# Ethernet.net
KiCad netlist of a schematic drawn in Altium Designer
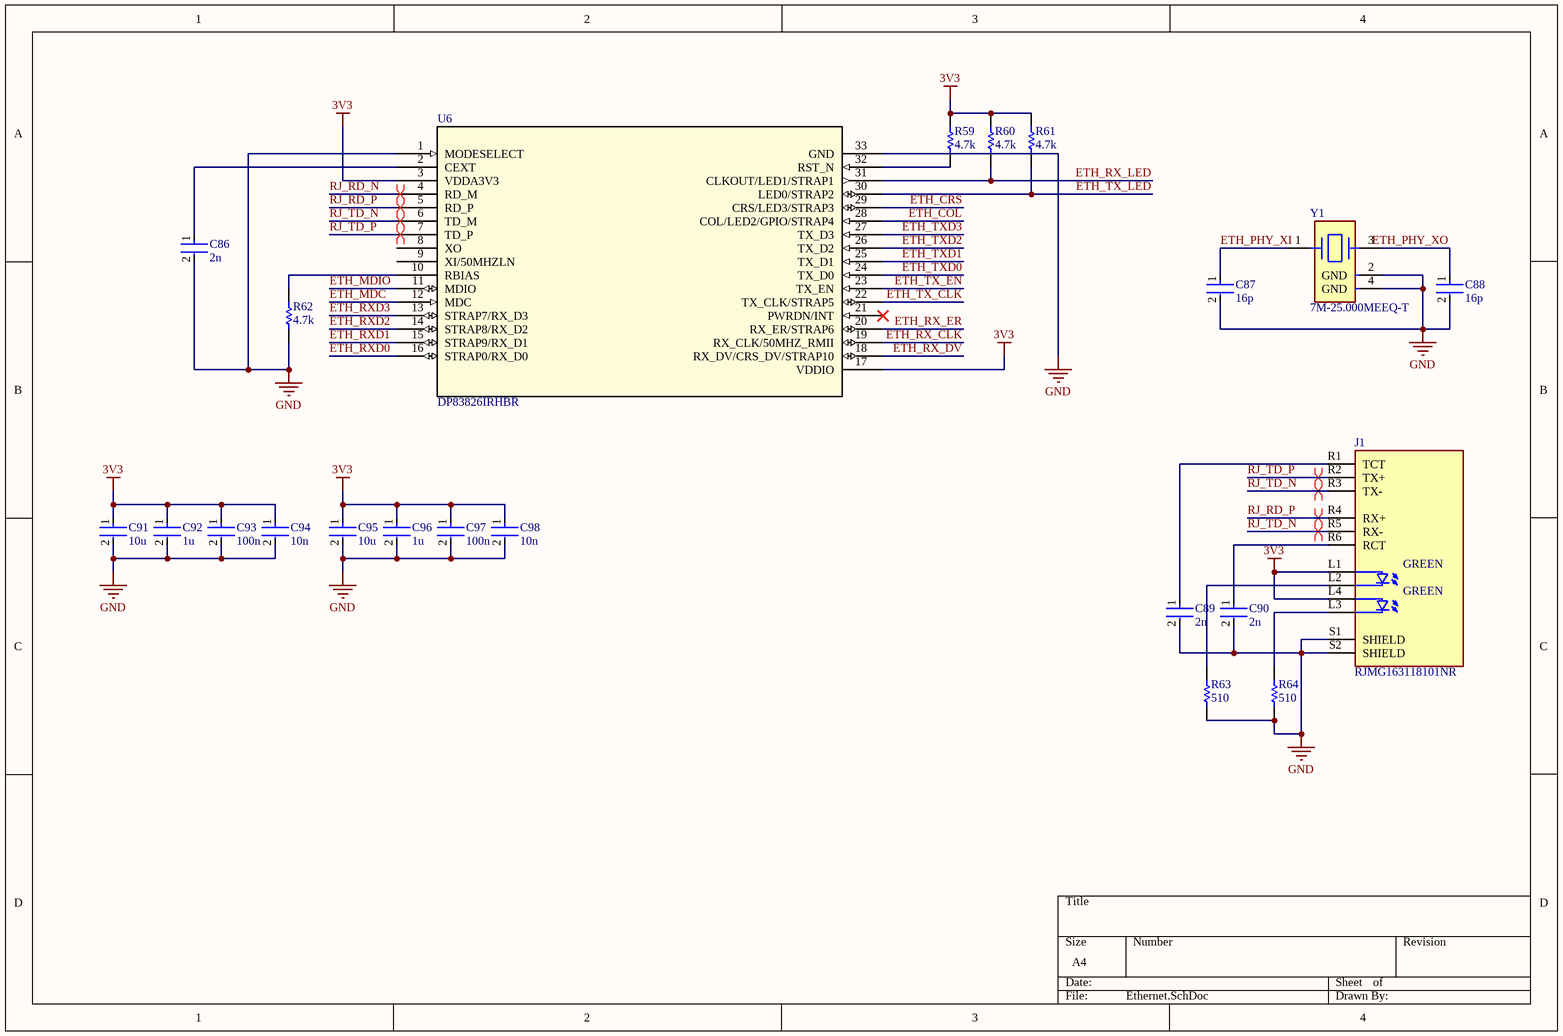
[diagram p0: Ethernet.SchDoc]

(export (version "E")
  (design (tool "Eeschema 10.0.6"))
  (components
    (comp (ref "C86")
      (value "2n")
      (footprint "FP-C0603C-CF-MFG")
      (description "CAP CER 0.1UF 50V X7R 0603")
      (fields (field (name "TOLERANCE") "0.1") (field (name "MANUFACTURER") "KEMET"))
      (libsource (lib "Altium Content Vault") (part "b4654b650e69147ec39a6b967a45e02"))
    )
    (comp (ref "C87")
      (value "16p")
      (footprint "FP-C0603C-CF-MFG")
      (description "CAP CER 0.1UF 50V X7R 0603")
      (fields (field (name "TOLERANCE") "0.1") (field (name "MANUFACTURER") "KEMET"))
      (libsource (lib "Altium Content Vault") (part "b4654b650e69147ec39a6b967a45e02"))
    )
    (comp (ref "C88")
      (value "16p")
      (footprint "FP-C0603C-CF-MFG")
      (description "CAP CER 0.1UF 50V X7R 0603")
      (fields (field (name "TOLERANCE") "0.1") (field (name "MANUFACTURER") "KEMET"))
      (libsource (lib "Altium Content Vault") (part "b4654b650e69147ec39a6b967a45e02"))
    )
    (comp (ref "C89")
      (value "2n")
      (footprint "FP-C0603C-CF-MFG")
      (description "CAP CER 0.1UF 50V X7R 0603")
      (fields (field (name "TOLERANCE") "0.1") (field (name "MANUFACTURER") "KEMET"))
      (libsource (lib "Altium Content Vault") (part "b4654b650e69147ec39a6b967a45e02"))
    )
    (comp (ref "C90")
      (value "2n")
      (footprint "FP-C0603C-CF-MFG")
      (description "CAP CER 0.1UF 50V X7R 0603")
      (fields (field (name "TOLERANCE") "0.1") (field (name "MANUFACTURER") "KEMET"))
      (libsource (lib "Altium Content Vault") (part "b4654b650e69147ec39a6b967a45e02"))
    )
    (comp (ref "C91")
      (value "10u")
      (footprint "FP-CC0805-0_85-MFG")
      (description "CAP CER 0.1UF 50V X7R 0805")
      (fields (field (name "TOLERANCE") "0.1") (field (name "MANUFACTURER PART NUMBER") "CC0805KRX7R9BB104"))
      (libsource (lib "Altium Content Vault") (part "11868f565c42a9108669ba33697ecf6"))
    )
    (comp (ref "C92")
      (value "1u")
      (footprint "FP-CC0805-0_85-MFG")
      (description "CAP CER 0.1UF 50V X7R 0805")
      (fields (field (name "TOLERANCE") "0.1") (field (name "MANUFACTURER PART NUMBER") "CC0805KRX7R9BB104"))
      (libsource (lib "Altium Content Vault") (part "11868f565c42a9108669ba33697ecf6"))
    )
    (comp (ref "C93")
      (value "100n")
      (footprint "FP-C0603C-CF-MFG")
      (description "CAP CER 0.1UF 50V X7R 0603")
      (fields (field (name "TOLERANCE") "0.1") (field (name "MANUFACTURER") "KEMET"))
      (libsource (lib "Altium Content Vault") (part "b4654b650e69147ec39a6b967a45e02"))
    )
    (comp (ref "C94")
      (value "10n")
      (footprint "FP-C0603C-CF-MFG")
      (description "CAP CER 0.1UF 50V X7R 0603")
      (fields (field (name "TOLERANCE") "0.1") (field (name "MANUFACTURER") "KEMET"))
      (libsource (lib "Altium Content Vault") (part "b4654b650e69147ec39a6b967a45e02"))
    )
    (comp (ref "C95")
      (value "10u")
      (footprint "FP-CC0805-0_85-MFG")
      (description "CAP CER 0.1UF 50V X7R 0805")
      (fields (field (name "TOLERANCE") "0.1") (field (name "MANUFACTURER PART NUMBER") "CC0805KRX7R9BB104"))
      (libsource (lib "Altium Content Vault") (part "11868f565c42a9108669ba33697ecf6"))
    )
    (comp (ref "C96")
      (value "1u")
      (footprint "FP-CC0805-0_85-MFG")
      (description "CAP CER 0.1UF 50V X7R 0805")
      (fields (field (name "TOLERANCE") "0.1") (field (name "MANUFACTURER PART NUMBER") "CC0805KRX7R9BB104"))
      (libsource (lib "Altium Content Vault") (part "11868f565c42a9108669ba33697ecf6"))
    )
    (comp (ref "C97")
      (value "100n")
      (footprint "FP-C0603C-CF-MFG")
      (description "CAP CER 0.1UF 50V X7R 0603")
      (fields (field (name "TOLERANCE") "0.1") (field (name "MANUFACTURER") "KEMET"))
      (libsource (lib "Altium Content Vault") (part "b4654b650e69147ec39a6b967a45e02"))
    )
    (comp (ref "C98")
      (value "10n")
      (footprint "FP-C0603C-CF-MFG")
      (description "CAP CER 0.1UF 50V X7R 0603")
      (fields (field (name "TOLERANCE") "0.1") (field (name "MANUFACTURER") "KEMET"))
      (libsource (lib "Altium Content Vault") (part "b4654b650e69147ec39a6b967a45e02"))
    )
    (comp (ref "J1")
      (value "RJMG163118101NR")
      (footprint "AMPHENOL_RJMG163118101NR")
      (libsource (lib "Master") (part "RJMG163118101NR"))
    )
    (comp (ref "R59")
      (value "4.7k")
      (footprint "RESC1609X50X30NL8T20")
      (description "Chip Resistor, 10 KOhm, +/- 1%, 100 mW, -55 to 155 degC, 0603 (1608 Metric), RoHS, Tape and Reel")
      (fields (field (name "MANUFACTURER") "Vishay Semiconductor"))
      (libsource (lib "Altium Content Vault") (part "RES-2"))
    )
    (comp (ref "R60")
      (value "4.7k")
      (footprint "RESC1609X50X30NL8T20")
      (description "Chip Resistor, 10 KOhm, +/- 1%, 100 mW, -55 to 155 degC, 0603 (1608 Metric), RoHS, Tape and Reel")
      (fields (field (name "MANUFACTURER") "Vishay Semiconductor"))
      (libsource (lib "Altium Content Vault") (part "RES-2"))
    )
    (comp (ref "R61")
      (value "4.7k")
      (footprint "RESC1609X50X30NL8T20")
      (description "Chip Resistor, 10 KOhm, +/- 1%, 100 mW, -55 to 155 degC, 0603 (1608 Metric), RoHS, Tape and Reel")
      (fields (field (name "MANUFACTURER") "Vishay Semiconductor"))
      (libsource (lib "Altium Content Vault") (part "RES-2"))
    )
    (comp (ref "R62")
      (value "4.7k")
      (footprint "RESC1609X50X30NL8T20")
      (description "Chip Resistor, 10 KOhm, +/- 1%, 100 mW, -55 to 155 degC, 0603 (1608 Metric), RoHS, Tape and Reel")
      (fields (field (name "MANUFACTURER") "Vishay Semiconductor"))
      (libsource (lib "Altium Content Vault") (part "RES-2"))
    )
    (comp (ref "R63")
      (value "510")
      (footprint "RESC1609X50X30NL8T20")
      (description "Chip Resistor, 10 KOhm, +/- 1%, 100 mW, -55 to 155 degC, 0603 (1608 Metric), RoHS, Tape and Reel")
      (fields (field (name "MANUFACTURER") "Vishay Semiconductor"))
      (libsource (lib "Altium Content Vault") (part "RES-2"))
    )
    (comp (ref "R64")
      (value "510")
      (footprint "RESC1609X50X30NL8T20")
      (description "Chip Resistor, 10 KOhm, +/- 1%, 100 mW, -55 to 155 degC, 0603 (1608 Metric), RoHS, Tape and Reel")
      (fields (field (name "MANUFACTURER") "Vishay Semiconductor"))
      (libsource (lib "Altium Content Vault") (part "RES-2"))
    )
    (comp (ref "U6")
      (value "DP83826IRHBR")
      (footprint "VQFN32_RHB_TEX")
      (description "No Description Available")
      (libsource (lib "Master") (part "DP83826IRHBR"))
    )
    (comp (ref "Y1")
      (value "7M-25.000MEEQ-T")
      (footprint "FP-7M-MFG")
      (description "Crystal 25MHz, 10ppm, 10pF, 50Ω")
      (fields (field (name "TOLERANCE") "10ppm"))
      (libsource (lib "Altium Content Vault") (part "41079aabb0e87794b56622915be14ed"))
    )
  )
  (nets
    (net (code "1") (name "/ETH_COL") (class "Default")
      (node (ref "U6") (pin "28") (pinfunction "COL/LED2/GPIO/STRAP4_28") (pintype "input"))
    )
    (net (code "2") (name "/ETH_CRS") (class "Default")
      (node (ref "U6") (pin "29") (pinfunction "CRS/LED3/STRAP3_29") (pintype "bidirectional"))
    )
    (net (code "3") (name "/ETH_MDC") (class "Default")
      (node (ref "U6") (pin "12") (pinfunction "MDC_12") (pintype "input"))
    )
    (net (code "4") (name "/ETH_MDIO") (class "Default")
      (node (ref "U6") (pin "11") (pinfunction "MDIO_11") (pintype "bidirectional"))
    )
    (net (code "5") (name "/ETH_PHY_XI") (class "Default")
      (node (ref "C87") (pin "1") (pinfunction "1_1") (pintype "passive"))
      (node (ref "Y1") (pin "1") (pinfunction "1_1") (pintype "passive"))
    )
    (net (code "6") (name "/ETH_PHY_XO") (class "Default")
      (node (ref "C88") (pin "1") (pinfunction "1_1") (pintype "passive"))
      (node (ref "Y1") (pin "3") (pinfunction "3_3") (pintype "passive"))
    )
    (net (code "7") (name "/ETH_RXD0") (class "Default")
      (node (ref "U6") (pin "16") (pinfunction "STRAP0/RX_D0_16") (pintype "bidirectional"))
    )
    (net (code "8") (name "/ETH_RXD1") (class "Default")
      (node (ref "U6") (pin "15") (pinfunction "STRAP9/RX_D1_15") (pintype "bidirectional"))
    )
    (net (code "9") (name "/ETH_RXD2") (class "Default")
      (node (ref "U6") (pin "14") (pinfunction "STRAP8/RX_D2_14") (pintype "bidirectional"))
    )
    (net (code "10") (name "/ETH_RXD3") (class "Default")
      (node (ref "U6") (pin "13") (pinfunction "STRAP7/RX_D3_13") (pintype "bidirectional"))
    )
    (net (code "11") (name "/ETH_RX_CLK") (class "Default")
      (node (ref "U6") (pin "19") (pinfunction "RX_CLK/50MHZ_RMII_19") (pintype "bidirectional"))
    )
    (net (code "12") (name "/ETH_RX_DV") (class "Default")
      (node (ref "U6") (pin "18") (pinfunction "RX_DV/CRS_DV/STRAP10_18") (pintype "bidirectional"))
    )
    (net (code "13") (name "/ETH_RX_ER") (class "Default")
      (node (ref "U6") (pin "20") (pinfunction "RX_ER/STRAP6_20") (pintype "bidirectional"))
    )
    (net (code "14") (name "/ETH_RX_LED") (class "Default")
      (node (ref "R60") (pin "1") (pinfunction "1_1") (pintype "passive"))
      (node (ref "U6") (pin "31") (pinfunction "CLKOUT/LED1/STRAP1_31") (pintype "output"))
    )
    (net (code "15") (name "/ETH_TXD0") (class "Default")
      (node (ref "U6") (pin "24") (pinfunction "TX_D0_24") (pintype "input"))
    )
    (net (code "16") (name "/ETH_TXD1") (class "Default")
      (node (ref "U6") (pin "25") (pinfunction "TX_D1_25") (pintype "input"))
    )
    (net (code "17") (name "/ETH_TXD2") (class "Default")
      (node (ref "U6") (pin "26") (pinfunction "TX_D2_26") (pintype "input"))
    )
    (net (code "18") (name "/ETH_TXD3") (class "Default")
      (node (ref "U6") (pin "27") (pinfunction "TX_D3_27") (pintype "input"))
    )
    (net (code "19") (name "/ETH_TX_CLK") (class "Default")
      (node (ref "U6") (pin "22") (pinfunction "TX_CLK/STRAP5_22") (pintype "bidirectional"))
    )
    (net (code "20") (name "/ETH_TX_EN") (class "Default")
      (node (ref "U6") (pin "23") (pinfunction "TX_EN_23") (pintype "input"))
    )
    (net (code "21") (name "/ETH_TX_LED") (class "Default")
      (node (ref "R61") (pin "1") (pinfunction "1_1") (pintype "passive"))
      (node (ref "U6") (pin "30") (pinfunction "LED0/STRAP2_30") (pintype "bidirectional"))
    )
    (net (code "22") (name "/RJ_RD_N") (class "Default")
      (node (ref "U6") (pin "4") (pinfunction "RD_M_4") (pintype "passive"))
    )
    (net (code "23") (name "/RJ_RD_P") (class "Default")
      (node (ref "J1") (pin "R4") (pinfunction "RX+_R4") (pintype "passive"))
      (node (ref "U6") (pin "5") (pinfunction "RD_P_5") (pintype "passive"))
    )
    (net (code "24") (name "/RJ_TD_N") (class "Default")
      (node (ref "J1") (pin "R3") (pinfunction "TX-_R3") (pintype "passive"))
      (node (ref "J1") (pin "R5") (pinfunction "RX-_R5") (pintype "passive"))
      (node (ref "U6") (pin "6") (pinfunction "TD_M_6") (pintype "passive"))
    )
    (net (code "25") (name "/RJ_TD_P") (class "Default")
      (node (ref "J1") (pin "R2") (pinfunction "TX+_R2") (pintype "passive"))
      (node (ref "U6") (pin "7") (pinfunction "TD_P_7") (pintype "passive"))
    )
    (net (code "26") (name "3V3") (class "Default")
      (node (ref "C91") (pin "1") (pinfunction "1_1") (pintype "passive"))
      (node (ref "C92") (pin "1") (pinfunction "1_1") (pintype "passive"))
      (node (ref "C93") (pin "1") (pinfunction "1_1") (pintype "passive"))
      (node (ref "C94") (pin "1") (pinfunction "1_1") (pintype "passive"))
      (node (ref "C95") (pin "1") (pinfunction "1_1") (pintype "passive"))
      (node (ref "C96") (pin "1") (pinfunction "1_1") (pintype "passive"))
      (node (ref "C97") (pin "1") (pinfunction "1_1") (pintype "passive"))
      (node (ref "C98") (pin "1") (pinfunction "1_1") (pintype "passive"))
      (node (ref "J1") (pin "L1") (pinfunction "LED1+_L1") (pintype "passive"))
      (node (ref "J1") (pin "L4") (pinfunction "LED2+_L4") (pintype "passive"))
      (node (ref "R59") (pin "2") (pinfunction "2_2") (pintype "passive"))
      (node (ref "R60") (pin "2") (pinfunction "2_2") (pintype "passive"))
      (node (ref "R61") (pin "2") (pinfunction "2_2") (pintype "passive"))
      (node (ref "U6") (pin "17") (pinfunction "VDDIO_17") (pintype "power_in"))
      (node (ref "U6") (pin "3") (pinfunction "VDDA3V3_3") (pintype "power_in"))
    )
    (net (code "27") (name "GND") (class "Default")
      (node (ref "C86") (pin "2") (pinfunction "2_2") (pintype "passive"))
      (node (ref "C87") (pin "2") (pinfunction "2_2") (pintype "passive"))
      (node (ref "C88") (pin "2") (pinfunction "2_2") (pintype "passive"))
      (node (ref "C89") (pin "2") (pinfunction "2_2") (pintype "passive"))
      (node (ref "C90") (pin "2") (pinfunction "2_2") (pintype "passive"))
      (node (ref "C91") (pin "2") (pinfunction "2_2") (pintype "passive"))
      (node (ref "C92") (pin "2") (pinfunction "2_2") (pintype "passive"))
      (node (ref "C93") (pin "2") (pinfunction "2_2") (pintype "passive"))
      (node (ref "C94") (pin "2") (pinfunction "2_2") (pintype "passive"))
      (node (ref "C95") (pin "2") (pinfunction "2_2") (pintype "passive"))
      (node (ref "C96") (pin "2") (pinfunction "2_2") (pintype "passive"))
      (node (ref "C97") (pin "2") (pinfunction "2_2") (pintype "passive"))
      (node (ref "C98") (pin "2") (pinfunction "2_2") (pintype "passive"))
      (node (ref "J1") (pin "S1") (pinfunction "SHIELD_S1") (pintype "passive"))
      (node (ref "J1") (pin "S2") (pinfunction "SHIELD_S2") (pintype "passive"))
      (node (ref "R62") (pin "1") (pinfunction "1_1") (pintype "passive"))
      (node (ref "R63") (pin "1") (pinfunction "1_1") (pintype "passive"))
      (node (ref "R64") (pin "1") (pinfunction "1_1") (pintype "passive"))
      (node (ref "U6") (pin "1") (pinfunction "MODESELECT_1") (pintype "input"))
      (node (ref "U6") (pin "33") (pinfunction "GND_33") (pintype "power_in"))
      (node (ref "Y1") (pin "2") (pinfunction "GND_2") (pintype "power_in"))
      (node (ref "Y1") (pin "4") (pinfunction "GND_4") (pintype "power_in"))
    )
    (net (code "28") (name "Net-(J1-LED1-)") (class "Default")
      (node (ref "J1") (pin "L2") (pinfunction "LED1-_L2") (pintype "passive"))
      (node (ref "R63") (pin "2") (pinfunction "2_2") (pintype "passive"))
    )
    (net (code "29") (name "Net-(J1-LED2-)") (class "Default")
      (node (ref "J1") (pin "L3") (pinfunction "LED2-_L3") (pintype "passive"))
      (node (ref "R64") (pin "2") (pinfunction "2_2") (pintype "passive"))
    )
    (net (code "30") (name "Net-(J1-RCT)") (class "Default")
      (node (ref "C90") (pin "1") (pinfunction "1_1") (pintype "passive"))
      (node (ref "J1") (pin "R6") (pinfunction "RCT_R6") (pintype "passive"))
    )
    (net (code "31") (name "Net-(J1-TCT)") (class "Default")
      (node (ref "C89") (pin "1") (pinfunction "1_1") (pintype "passive"))
      (node (ref "J1") (pin "R1") (pinfunction "TCT_R1") (pintype "passive"))
    )
    (net (code "32") (name "Net-(U6-CEXT)") (class "Default")
      (node (ref "C86") (pin "1") (pinfunction "1_1") (pintype "passive"))
      (node (ref "U6") (pin "2") (pinfunction "CEXT_2") (pintype "passive"))
    )
    (net (code "33") (name "Net-(U6-RBIAS)") (class "Default")
      (node (ref "R62") (pin "2") (pinfunction "2_2") (pintype "passive"))
      (node (ref "U6") (pin "10") (pinfunction "RBIAS_10") (pintype "passive"))
    )
    (net (code "34") (name "Net-(U6-RST_N)") (class "Default")
      (node (ref "R59") (pin "1") (pinfunction "1_1") (pintype "passive"))
      (node (ref "U6") (pin "32") (pinfunction "RST_N_32") (pintype "input"))
    )
    (net (code "35") (name "unconnected-(U6-PWRDN{slash}INT-Pad21)") (class "Default")
      (node (ref "U6") (pin "21") (pinfunction "PWRDN/INT_21") (pintype "input+no_connect"))
    )
    (net (code "36") (name "unconnected-(U6-XI{slash}50MHZLN-Pad9)") (class "Default")
      (node (ref "U6") (pin "9") (pinfunction "XI/50MHZLN_9") (pintype "passive"))
    )
    (net (code "37") (name "unconnected-(U6-XO-Pad8)") (class "Default")
      (node (ref "U6") (pin "8") (pinfunction "XO_8") (pintype "passive"))
    )
  )
)
